# PowerModule.net
KiCad netlist of a schematic drawn in EAGLE
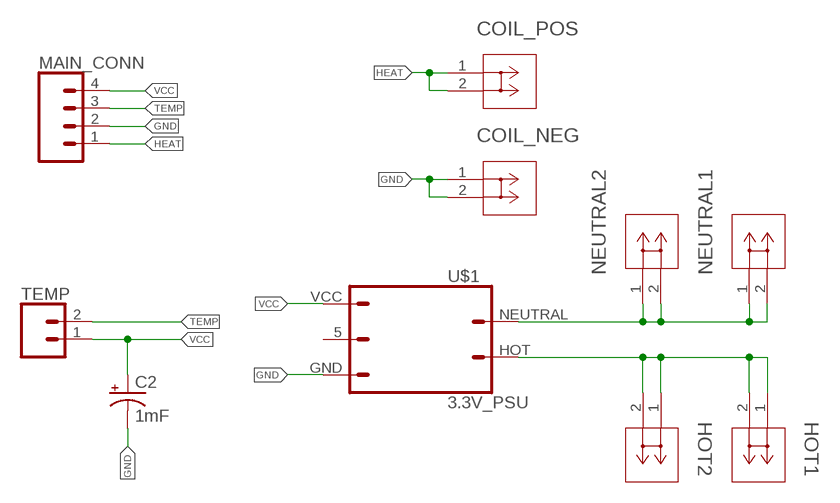
[diagram p0: schematic, sheet 1]

(export (version "E")
  (design (tool "Eeschema 10.0.6"))
  (components
    (comp (ref "C2")
      (value "1mF")
      (footprint "eagle-import:CPOL-RADIAL-5MM-10MM")
      (libsource (lib "eagle-import") (part "1000UF-RADIAL-5MM-25V-20%"))
    )
    (comp (ref "COIL_NEG")
      (value "1287")
      (footprint "eagle-import:CONN_1287_KEY")
      (fields (field (name "COPYRIGHT") "Copyright (C) 2022 Ultra Librarian. All rights reserved."))
      (libsource (lib "eagle-import") (part "1287"))
    )
    (comp (ref "COIL_POS")
      (value "1287")
      (footprint "eagle-import:CONN_1287_KEY")
      (fields (field (name "COPYRIGHT") "Copyright (C) 2022 Ultra Librarian. All rights reserved."))
      (libsource (lib "eagle-import") (part "1287"))
    )
    (comp (ref "HOT1")
      (value "1287")
      (footprint "eagle-import:CONN_1287_KEY")
      (fields (field (name "COPYRIGHT") "Copyright (C) 2022 Ultra Librarian. All rights reserved."))
      (libsource (lib "eagle-import") (part "1287"))
    )
    (comp (ref "HOT2")
      (value "1287")
      (footprint "eagle-import:CONN_1287_KEY")
      (fields (field (name "COPYRIGHT") "Copyright (C) 2022 Ultra Librarian. All rights reserved."))
      (libsource (lib "eagle-import") (part "1287"))
    )
    (comp (ref "MAIN_CONN")
      (value "CONN_04PTH")
      (footprint "eagle-import:1X04")
      (libsource (lib "eagle-import") (part "CONN_04PTH"))
    )
    (comp (ref "NEUTRAL1")
      (value "1287")
      (footprint "eagle-import:CONN_1287_KEY")
      (fields (field (name "COPYRIGHT") "Copyright (C) 2022 Ultra Librarian. All rights reserved."))
      (libsource (lib "eagle-import") (part "1287"))
    )
    (comp (ref "NEUTRAL2")
      (value "1287")
      (footprint "eagle-import:CONN_1287_KEY")
      (fields (field (name "COPYRIGHT") "Copyright (C) 2022 Ultra Librarian. All rights reserved."))
      (libsource (lib "eagle-import") (part "1287"))
    )
    (comp (ref "TEMP")
      (value "CONN_02")
      (footprint "eagle-import:1X02")
      (libsource (lib "eagle-import") (part "CONN_02"))
    )
    (comp (ref "U$1")
      (value "3.3V_PSU")
      (footprint "eagle-import:1X03")
      (libsource (lib "eagle-import") (part "3.3V_PSU"))
    )
  )
  (nets
    (net (code "1") (name "GND") (class "Default")
      (node (ref "C2") (pin "-") (pinfunction "-_-") (pintype "passive"))
      (node (ref "COIL_NEG") (pin "1") (pinfunction "1_1") (pintype "passive"))
      (node (ref "COIL_NEG") (pin "2") (pinfunction "2_2") (pintype "passive"))
      (node (ref "MAIN_CONN") (pin "2") (pinfunction "2_2") (pintype "passive"))
      (node (ref "U$1") (pin "GND") (pinfunction "GND_GND") (pintype "passive"))
    )
    (net (code "2") (name "HEAT") (class "Default")
      (node (ref "COIL_POS") (pin "1") (pinfunction "1_1") (pintype "passive"))
      (node (ref "COIL_POS") (pin "2") (pinfunction "2_2") (pintype "passive"))
      (node (ref "MAIN_CONN") (pin "1") (pinfunction "1_1") (pintype "passive"))
    )
    (net (code "3") (name "Net-(HOT1-Pad1)") (class "Default")
      (node (ref "HOT1") (pin "1") (pinfunction "1_1") (pintype "passive"))
      (node (ref "HOT1") (pin "2") (pinfunction "2_2") (pintype "passive"))
      (node (ref "HOT2") (pin "1") (pinfunction "1_1") (pintype "passive"))
      (node (ref "HOT2") (pin "2") (pinfunction "2_2") (pintype "passive"))
      (node (ref "U$1") (pin "HOT") (pinfunction "HOT_HOT") (pintype "passive"))
    )
    (net (code "4") (name "Net-(NEUTRAL1-Pad1)") (class "Default")
      (node (ref "NEUTRAL1") (pin "1") (pinfunction "1_1") (pintype "passive"))
      (node (ref "NEUTRAL1") (pin "2") (pinfunction "2_2") (pintype "passive"))
      (node (ref "NEUTRAL2") (pin "1") (pinfunction "1_1") (pintype "passive"))
      (node (ref "NEUTRAL2") (pin "2") (pinfunction "2_2") (pintype "passive"))
      (node (ref "U$1") (pin "NEUTRAL") (pinfunction "NEUTRAL_NEUTRAL") (pintype "passive"))
    )
    (net (code "5") (name "TEMP") (class "Default")
      (node (ref "MAIN_CONN") (pin "3") (pinfunction "3_3") (pintype "passive"))
      (node (ref "TEMP") (pin "2") (pinfunction "2_2") (pintype "passive"))
    )
    (net (code "6") (name "VCC") (class "Default")
      (node (ref "C2") (pin "+") (pinfunction "+_+") (pintype "passive"))
      (node (ref "MAIN_CONN") (pin "4") (pinfunction "4_4") (pintype "passive"))
      (node (ref "TEMP") (pin "1") (pinfunction "1_1") (pintype "passive"))
      (node (ref "U$1") (pin "VCC") (pinfunction "VCC_VCC") (pintype "passive"))
    )
    (net (code "7") (name "unconnected-(U$1-6-Pad5)") (class "Default")
      (node (ref "U$1") (pin "5") (pinfunction "6_5") (pintype "passive"))
    )
  )
)
